# main.net
KiCad netlist of a schematic drawn in Altium Designer
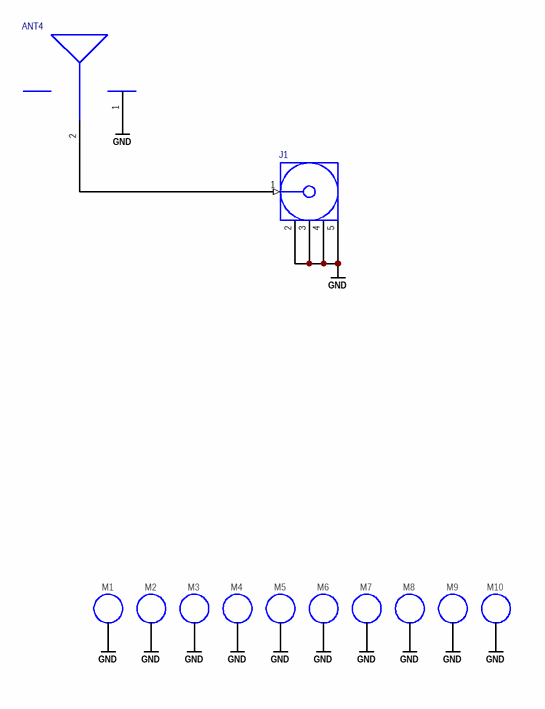
[diagram p0: main.SchDoc]

(export (version "E")
  (design (tool "Eeschema 10.0.6"))
  (components
    (comp (ref "ANT4")
      (value "antenna_plane")
      (footprint "antenna_plane")
      (fields (field (name "MANUFACTURER") "Siglabs"))
      (libsource (lib "higgsant") (part "antenna_plane"))
    )
    (comp (ref "J1")
      (value "142146")
      (footprint "amphenol:142146")
      (description "Connector; RF Coaxial, SMB, Thru-Hole; 5 Position; Right-Angle")
      (fields (field (name "MANUFACTURER") "Amphenol RF"))
      (libsource (lib "Miscellaneous Connectors") (part "COAX-F"))
    )
    (comp (ref "M1")
      (value "MOUNT")
      (footprint "MOUNTM3")
      (description "M3 Standard Fit Hole")
      (libsource (lib "copper_suicide") (part "MOUNT"))
    )
    (comp (ref "M2")
      (value "MOUNT")
      (footprint "MOUNTM3")
      (description "M3 Standard Fit Hole")
      (libsource (lib "copper_suicide") (part "MOUNT"))
    )
    (comp (ref "M3")
      (value "MOUNT")
      (footprint "MOUNTM3")
      (description "M3 Standard Fit Hole")
      (libsource (lib "copper_suicide") (part "MOUNT"))
    )
    (comp (ref "M4")
      (value "MOUNT")
      (footprint "MOUNTM3")
      (description "M3 Standard Fit Hole")
      (libsource (lib "copper_suicide") (part "MOUNT"))
    )
    (comp (ref "M5")
      (value "MOUNT")
      (footprint "MOUNTM3")
      (description "M3 Standard Fit Hole")
      (libsource (lib "copper_suicide") (part "MOUNT"))
    )
    (comp (ref "M6")
      (value "MOUNT")
      (footprint "MOUNTM3")
      (description "M3 Standard Fit Hole")
      (libsource (lib "copper_suicide") (part "MOUNT"))
    )
    (comp (ref "M7")
      (value "MOUNT")
      (footprint "MOUNTM3")
      (description "M3 Standard Fit Hole")
      (libsource (lib "copper_suicide") (part "MOUNT"))
    )
    (comp (ref "M8")
      (value "MOUNT")
      (footprint "MOUNTM3")
      (description "M3 Standard Fit Hole")
      (libsource (lib "copper_suicide") (part "MOUNT"))
    )
    (comp (ref "M9")
      (value "MOUNT")
      (footprint "MOUNTM3")
      (description "M3 Standard Fit Hole")
      (libsource (lib "copper_suicide") (part "MOUNT"))
    )
    (comp (ref "M10")
      (value "MOUNT")
      (footprint "MOUNTM3")
      (description "M3 Standard Fit Hole")
      (libsource (lib "copper_suicide") (part "MOUNT"))
    )
  )
  (nets
    (net (code "1") (name "GND") (class "Default")
      (node (ref "ANT4") (pin "1") (pinfunction "1_1") (pintype "passive"))
      (node (ref "J1") (pin "2") (pinfunction "GND_2") (pintype "power_in"))
      (node (ref "J1") (pin "3") (pinfunction "GND_3") (pintype "power_in"))
      (node (ref "J1") (pin "4") (pinfunction "GND_4") (pintype "power_in"))
      (node (ref "J1") (pin "5") (pinfunction "GND_5") (pintype "power_in"))
      (node (ref "M1") (pin "1") (pinfunction "MNT_1") (pintype "passive"))
      (node (ref "M10") (pin "1") (pinfunction "MNT_1") (pintype "passive"))
      (node (ref "M2") (pin "1") (pinfunction "MNT_1") (pintype "passive"))
      (node (ref "M3") (pin "1") (pinfunction "MNT_1") (pintype "passive"))
      (node (ref "M4") (pin "1") (pinfunction "MNT_1") (pintype "passive"))
      (node (ref "M5") (pin "1") (pinfunction "MNT_1") (pintype "passive"))
      (node (ref "M6") (pin "1") (pinfunction "MNT_1") (pintype "passive"))
      (node (ref "M7") (pin "1") (pinfunction "MNT_1") (pintype "passive"))
      (node (ref "M8") (pin "1") (pinfunction "MNT_1") (pintype "passive"))
      (node (ref "M9") (pin "1") (pinfunction "MNT_1") (pintype "passive"))
    )
    (net (code "2") (name "Net-(J1-Signal)") (class "Default")
      (node (ref "ANT4") (pin "2") (pinfunction "2_2") (pintype "passive"))
      (node (ref "J1") (pin "1") (pinfunction "Signal_1") (pintype "input"))
    )
  )
)
